# Arduino_S3v3_R2_b.net
KiCad netlist of a schematic drawn in EAGLE
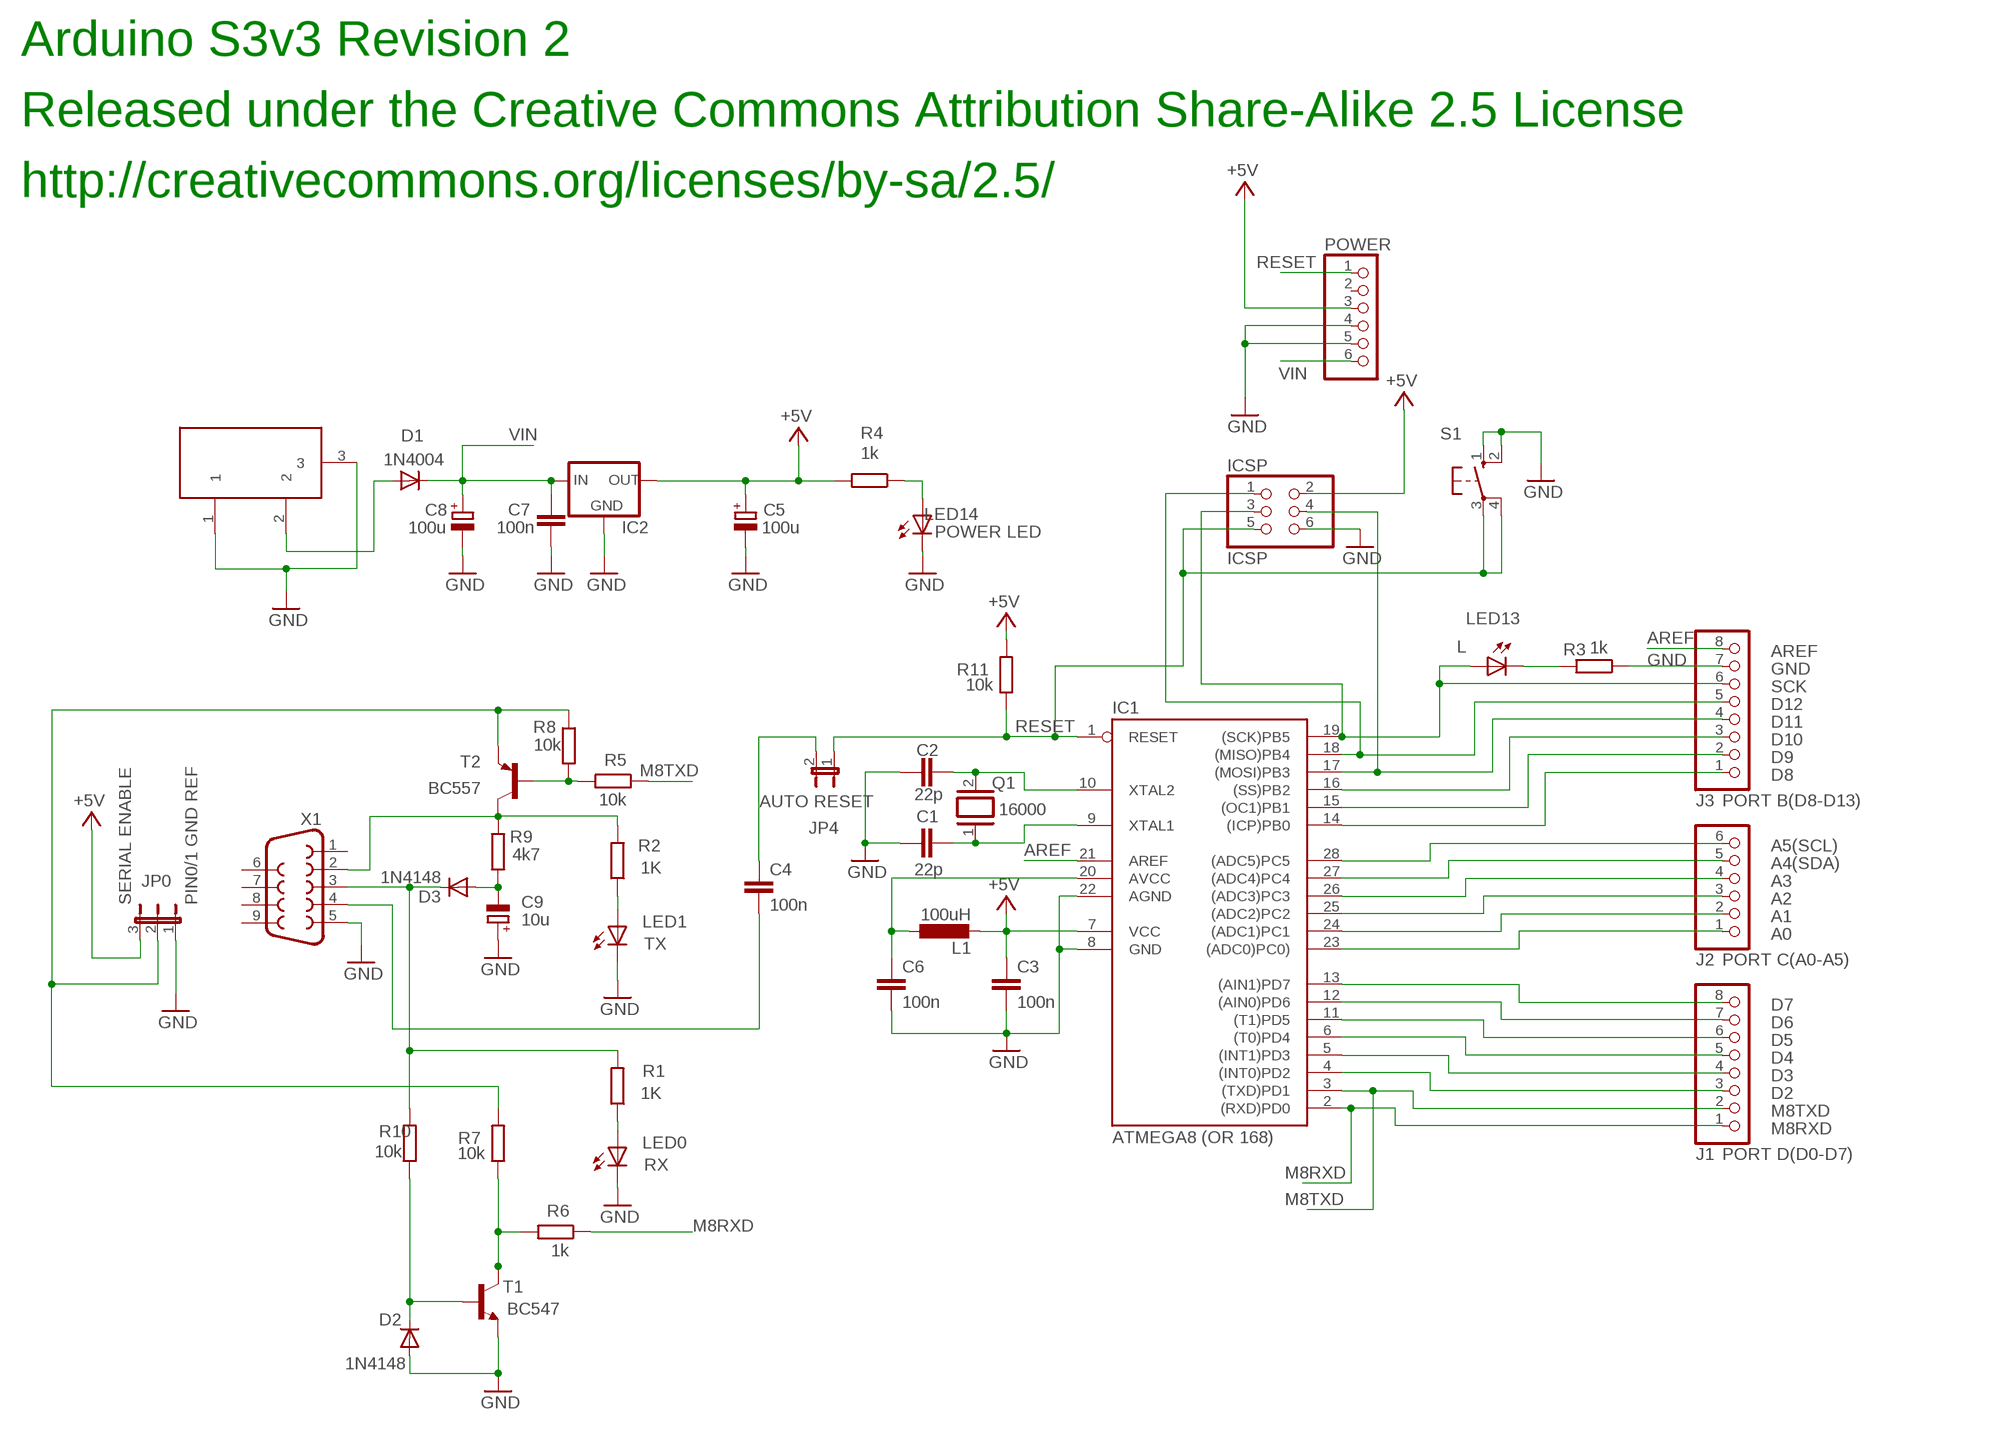
[diagram p0: schematic, sheet 1]

(export (version "E")
  (design (tool "Eeschema 10.0.6"))
  (components
    (comp (ref "C1")
      (value "22p")
      (footprint "eagle-import:C025-024X044")
      (libsource (lib "eagle-import") (part "C-EU025-024X044"))
    )
    (comp (ref "C2")
      (value "22p")
      (footprint "eagle-import:C025-024X044")
      (libsource (lib "eagle-import") (part "C-EU025-024X044"))
    )
    (comp (ref "C3")
      (value "100n")
      (footprint "eagle-import:C050-025X075")
      (libsource (lib "eagle-import") (part "C-EU050-025X075"))
    )
    (comp (ref "C4")
      (value "100n")
      (footprint "eagle-import:C050-025X075")
      (libsource (lib "eagle-import") (part "C-EU050-025X075"))
    )
    (comp (ref "C5")
      (value "100u")
      (footprint "eagle-import:E3,5-8")
      (libsource (lib "eagle-import") (part "CPOL-EUE3.5-8"))
    )
    (comp (ref "C6")
      (value "100n")
      (footprint "eagle-import:C050-025X075")
      (libsource (lib "eagle-import") (part "C-EU050-025X075"))
    )
    (comp (ref "C7")
      (value "100n")
      (footprint "eagle-import:C050-025X075")
      (libsource (lib "eagle-import") (part "C-EU050-025X075"))
    )
    (comp (ref "C8")
      (value "100u")
      (footprint "eagle-import:E3,5-8")
      (libsource (lib "eagle-import") (part "CPOL-EUE3.5-8"))
    )
    (comp (ref "C9")
      (value "10u")
      (footprint "eagle-import:E5-6")
      (libsource (lib "eagle-import") (part "CPOL-EUE5-6"))
    )
    (comp (ref "D1")
      (value "1N4004")
      (footprint "eagle-import:DO41-10")
      (libsource (lib "eagle-import") (part "1N4004"))
    )
    (comp (ref "D2")
      (value "1N4148")
      (footprint "eagle-import:DO35-10")
      (libsource (lib "eagle-import") (part "1N4148"))
    )
    (comp (ref "D3")
      (value "1N4148")
      (footprint "eagle-import:DO35-10")
      (libsource (lib "eagle-import") (part "1N4148"))
    )
    (comp (ref "DC1")
      (value "DC21MMX")
      (footprint "eagle-import:DC-21MM")
      (libsource (lib "eagle-import") (part "DC21MMX"))
    )
    (comp (ref "IC1")
      (value "ATMEGA8 (OR 168)")
      (footprint "eagle-import:DIL28-3")
      (libsource (lib "eagle-import") (part "AT90S4433P"))
    )
    (comp (ref "IC2")
      (value "78XXL")
      (footprint "eagle-import:78XXL")
      (libsource (lib "eagle-import") (part "78XXL"))
    )
    (comp (ref "ICSP")
      (value "ICSP")
      (footprint "eagle-import:2X03")
      (libsource (lib "eagle-import") (part "PINHD-2X3"))
    )
    (comp (ref "J1")
      (value "PORT D(D0-D7)")
      (footprint "eagle-import:1X08")
      (libsource (lib "eagle-import") (part "PINHD-1X8"))
    )
    (comp (ref "J2")
      (value "PORT C(A0-A5)")
      (footprint "eagle-import:1X06")
      (libsource (lib "eagle-import") (part "PINHD-1X6"))
    )
    (comp (ref "J3")
      (value "PORT B(D8-D13)")
      (footprint "eagle-import:1X08")
      (libsource (lib "eagle-import") (part "PINHD-1X8"))
    )
    (comp (ref "JP0")
      (value "JP2W")
      (footprint "eagle-import:JP2W")
      (libsource (lib "eagle-import") (part "JP2W"))
    )
    (comp (ref "JP4")
      (value "AUTO RESET")
      (footprint "eagle-import:JP1W")
      (libsource (lib "eagle-import") (part "JP1W"))
    )
    (comp (ref "L1")
      (value "100uH")
      (footprint "eagle-import:0204_5")
      (libsource (lib "eagle-import") (part "L-EU0204/5"))
    )
    (comp (ref "LED0")
      (value "RX")
      (footprint "eagle-import:LED3MM")
      (libsource (lib "eagle-import") (part "LED3MM"))
    )
    (comp (ref "LED1")
      (value "TX")
      (footprint "eagle-import:LED3MM")
      (libsource (lib "eagle-import") (part "LED3MM"))
    )
    (comp (ref "LED13")
      (value "L")
      (footprint "eagle-import:LED3MM")
      (libsource (lib "eagle-import") (part "LED3MM"))
    )
    (comp (ref "LED14")
      (value "POWER LED")
      (footprint "eagle-import:LED3MM")
      (libsource (lib "eagle-import") (part "LED3MM"))
    )
    (comp (ref "POWER")
      (value "PINHD-1X6")
      (footprint "eagle-import:1X06")
      (libsource (lib "eagle-import") (part "PINHD-1X6"))
    )
    (comp (ref "Q1")
      (value "16000")
      (footprint "eagle-import:QS")
      (libsource (lib "eagle-import") (part "XTAL/S"))
    )
    (comp (ref "R1")
      (value "1K")
      (footprint "eagle-import:0207_10")
      (libsource (lib "eagle-import") (part "R-EU_0207/10"))
    )
    (comp (ref "R2")
      (value "1K")
      (footprint "eagle-import:0207_10")
      (libsource (lib "eagle-import") (part "R-EU_0207/10"))
    )
    (comp (ref "R3")
      (value "1k")
      (footprint "eagle-import:0207_10")
      (libsource (lib "eagle-import") (part "R-EU_0207/10"))
    )
    (comp (ref "R4")
      (value "1k")
      (footprint "eagle-import:0207_10")
      (libsource (lib "eagle-import") (part "R-EU_0207/10"))
    )
    (comp (ref "R5")
      (value "10k")
      (footprint "eagle-import:0207_10")
      (libsource (lib "eagle-import") (part "R-EU_0207/10"))
    )
    (comp (ref "R6")
      (value "1k")
      (footprint "eagle-import:0207_10")
      (libsource (lib "eagle-import") (part "R-EU_0207/10"))
    )
    (comp (ref "R7")
      (value "10k")
      (footprint "eagle-import:0207_10")
      (libsource (lib "eagle-import") (part "R-EU_0207/10"))
    )
    (comp (ref "R8")
      (value "10k")
      (footprint "eagle-import:0207_10")
      (libsource (lib "eagle-import") (part "R-EU_0207/10"))
    )
    (comp (ref "R9")
      (value "4k7")
      (footprint "eagle-import:0207_10")
      (libsource (lib "eagle-import") (part "R-EU_0207/10"))
    )
    (comp (ref "R10")
      (value "10k")
      (footprint "eagle-import:0207_10")
      (libsource (lib "eagle-import") (part "R-EU_0207/10"))
    )
    (comp (ref "R11")
      (value "10k")
      (footprint "eagle-import:0207_10")
      (libsource (lib "eagle-import") (part "R-EU_0207/10"))
    )
    (comp (ref "S1")
      (value "10-XX")
      (footprint "eagle-import:B3F-10XX")
      (libsource (lib "eagle-import") (part "10-XX"))
    )
    (comp (ref "T1")
      (value "BC547")
      (footprint "eagle-import:TO92")
      (libsource (lib "eagle-import") (part "BC547"))
    )
    (comp (ref "T2")
      (value "BC557")
      (footprint "eagle-import:TO92-EBC")
      (libsource (lib "eagle-import") (part "-PNP-TO92-EBCBC557B"))
    )
    (comp (ref "X1")
      (value "F09H")
      (footprint "eagle-import:F09H")
      (libsource (lib "eagle-import") (part "F09H"))
    )
  )
  (nets
    (net (code "1") (name "+5V") (class "Default")
      (node (ref "C3") (pin "1") (pinfunction "1_1") (pintype "passive"))
      (node (ref "C5") (pin "+") (pinfunction "+_+") (pintype "passive"))
      (node (ref "IC1") (pin "7") (pinfunction "VCC_7") (pintype "power_in"))
      (node (ref "IC2") (pin "OUT") (pinfunction "OUT_OUT") (pintype "passive"))
      (node (ref "ICSP") (pin "2") (pinfunction "2_2") (pintype "passive"))
      (node (ref "JP0") (pin "3") (pinfunction "3_3") (pintype "passive"))
      (node (ref "L1") (pin "2") (pinfunction "2_2") (pintype "passive"))
      (node (ref "POWER") (pin "3") (pinfunction "3_3") (pintype "passive"))
      (node (ref "R11") (pin "2") (pinfunction "2_2") (pintype "passive"))
      (node (ref "R4") (pin "2") (pinfunction "2_2") (pintype "passive"))
    )
    (net (code "2") (name "/A0") (class "Default")
      (node (ref "IC1") (pin "23") (pinfunction "(ADC0)PC0)_23") (pintype "bidirectional"))
      (node (ref "J2") (pin "1") (pinfunction "1_1") (pintype "passive"))
    )
    (net (code "3") (name "/A1") (class "Default")
      (node (ref "IC1") (pin "24") (pinfunction "(ADC1)PC1_24") (pintype "bidirectional"))
      (node (ref "J2") (pin "2") (pinfunction "2_2") (pintype "passive"))
    )
    (net (code "4") (name "/A2") (class "Default")
      (node (ref "IC1") (pin "25") (pinfunction "(ADC2)PC2_25") (pintype "bidirectional"))
      (node (ref "J2") (pin "3") (pinfunction "3_3") (pintype "passive"))
    )
    (net (code "5") (name "/A3") (class "Default")
      (node (ref "IC1") (pin "26") (pinfunction "(ADC3)PC3_26") (pintype "bidirectional"))
      (node (ref "J2") (pin "4") (pinfunction "4_4") (pintype "passive"))
    )
    (net (code "6") (name "/A4(SDA)") (class "Default")
      (node (ref "IC1") (pin "27") (pinfunction "(ADC4)PC4_27") (pintype "bidirectional"))
      (node (ref "J2") (pin "5") (pinfunction "5_5") (pintype "passive"))
    )
    (net (code "7") (name "/A5(SCL)") (class "Default")
      (node (ref "IC1") (pin "28") (pinfunction "(ADC5)PC5_28") (pintype "bidirectional"))
      (node (ref "J2") (pin "6") (pinfunction "6_6") (pintype "passive"))
    )
    (net (code "8") (name "/AREF") (class "Default")
      (node (ref "IC1") (pin "21") (pinfunction "AREF_21") (pintype "power_in"))
      (node (ref "J3") (pin "8") (pinfunction "8_8") (pintype "passive"))
    )
    (net (code "9") (name "/D2") (class "Default")
      (node (ref "IC1") (pin "4") (pinfunction "(INT0)PD2_4") (pintype "bidirectional"))
      (node (ref "J1") (pin "3") (pinfunction "3_3") (pintype "passive"))
    )
    (net (code "10") (name "/D3") (class "Default")
      (node (ref "IC1") (pin "5") (pinfunction "(INT1)PD3_5") (pintype "bidirectional"))
      (node (ref "J1") (pin "4") (pinfunction "4_4") (pintype "passive"))
    )
    (net (code "11") (name "/D4") (class "Default")
      (node (ref "IC1") (pin "6") (pinfunction "(T0)PD4_6") (pintype "bidirectional"))
      (node (ref "J1") (pin "5") (pinfunction "5_5") (pintype "passive"))
    )
    (net (code "12") (name "/D5") (class "Default")
      (node (ref "IC1") (pin "11") (pinfunction "(T1)PD5_11") (pintype "bidirectional"))
      (node (ref "J1") (pin "6") (pinfunction "6_6") (pintype "passive"))
    )
    (net (code "13") (name "/D6") (class "Default")
      (node (ref "IC1") (pin "12") (pinfunction "(AIN0)PD6_12") (pintype "bidirectional"))
      (node (ref "J1") (pin "7") (pinfunction "7_7") (pintype "passive"))
    )
    (net (code "14") (name "/D7") (class "Default")
      (node (ref "IC1") (pin "13") (pinfunction "(AIN1)PD7_13") (pintype "bidirectional"))
      (node (ref "J1") (pin "8") (pinfunction "8_8") (pintype "passive"))
    )
    (net (code "15") (name "/D8") (class "Default")
      (node (ref "IC1") (pin "14") (pinfunction "(ICP)PB0_14") (pintype "bidirectional"))
      (node (ref "J3") (pin "1") (pinfunction "1_1") (pintype "passive"))
    )
    (net (code "16") (name "/D9") (class "Default")
      (node (ref "IC1") (pin "15") (pinfunction "(OC1)PB1_15") (pintype "bidirectional"))
      (node (ref "J3") (pin "2") (pinfunction "2_2") (pintype "passive"))
    )
    (net (code "17") (name "/D10") (class "Default")
      (node (ref "IC1") (pin "16") (pinfunction "(SS)PB2_16") (pintype "bidirectional"))
      (node (ref "J3") (pin "3") (pinfunction "3_3") (pintype "passive"))
    )
    (net (code "18") (name "/D11") (class "Default")
      (node (ref "IC1") (pin "17") (pinfunction "(MOSI)PB3_17") (pintype "bidirectional"))
      (node (ref "ICSP") (pin "4") (pinfunction "4_4") (pintype "passive"))
      (node (ref "J3") (pin "4") (pinfunction "4_4") (pintype "passive"))
    )
    (net (code "19") (name "/D12") (class "Default")
      (node (ref "IC1") (pin "18") (pinfunction "(MISO)PB4_18") (pintype "bidirectional"))
      (node (ref "ICSP") (pin "1") (pinfunction "1_1") (pintype "passive"))
      (node (ref "J3") (pin "5") (pinfunction "5_5") (pintype "passive"))
    )
    (net (code "20") (name "/M8RXD") (class "Default")
      (node (ref "IC1") (pin "2") (pinfunction "(RXD)PD0_2") (pintype "bidirectional"))
      (node (ref "J1") (pin "1") (pinfunction "1_1") (pintype "passive"))
      (node (ref "R6") (pin "1") (pinfunction "1_1") (pintype "passive"))
    )
    (net (code "21") (name "/M8TXD") (class "Default")
      (node (ref "IC1") (pin "3") (pinfunction "(TXD)PD1_3") (pintype "bidirectional"))
      (node (ref "J1") (pin "2") (pinfunction "2_2") (pintype "passive"))
      (node (ref "R5") (pin "1") (pinfunction "1_1") (pintype "passive"))
    )
    (net (code "22") (name "/RESET") (class "Default")
      (node (ref "IC1") (pin "1") (pinfunction "RESET_1") (pintype "input"))
      (node (ref "ICSP") (pin "5") (pinfunction "5_5") (pintype "passive"))
      (node (ref "JP4") (pin "1") (pinfunction "1_1") (pintype "passive"))
      (node (ref "POWER") (pin "1") (pinfunction "1_1") (pintype "passive"))
      (node (ref "R11") (pin "1") (pinfunction "1_1") (pintype "passive"))
      (node (ref "S1") (pin "3") (pinfunction "P_3") (pintype "passive"))
      (node (ref "S1") (pin "4") (pinfunction "P1_4") (pintype "passive"))
    )
    (net (code "23") (name "/SCK") (class "Default")
      (node (ref "IC1") (pin "19") (pinfunction "(SCK)PB5_19") (pintype "bidirectional"))
      (node (ref "ICSP") (pin "3") (pinfunction "3_3") (pintype "passive"))
      (node (ref "J3") (pin "6") (pinfunction "6_6") (pintype "passive"))
      (node (ref "LED13") (pin "A") (pinfunction "A_A") (pintype "passive"))
    )
    (net (code "24") (name "/VIN") (class "Default")
      (node (ref "C7") (pin "2") (pinfunction "2_2") (pintype "passive"))
      (node (ref "C8") (pin "+") (pinfunction "+_+") (pintype "passive"))
      (node (ref "D1") (pin "C") (pinfunction "C_C") (pintype "passive"))
      (node (ref "IC2") (pin "IN") (pinfunction "IN_IN") (pintype "input"))
      (node (ref "POWER") (pin "6") (pinfunction "6_6") (pintype "passive"))
    )
    (net (code "25") (name "GND") (class "Default")
      (node (ref "C1") (pin "1") (pinfunction "1_1") (pintype "passive"))
      (node (ref "C2") (pin "1") (pinfunction "1_1") (pintype "passive"))
      (node (ref "C3") (pin "2") (pinfunction "2_2") (pintype "passive"))
      (node (ref "C5") (pin "-") (pinfunction "-_-") (pintype "passive"))
      (node (ref "C6") (pin "2") (pinfunction "2_2") (pintype "passive"))
      (node (ref "C7") (pin "1") (pinfunction "1_1") (pintype "passive"))
      (node (ref "C8") (pin "-") (pinfunction "-_-") (pintype "passive"))
      (node (ref "C9") (pin "+") (pinfunction "+_+") (pintype "passive"))
      (node (ref "D2") (pin "A") (pinfunction "A_A") (pintype "passive"))
      (node (ref "DC1") (pin "1") (pinfunction "1_1") (pintype "power_in"))
      (node (ref "DC1") (pin "3") (pinfunction "3_3") (pintype "power_in"))
      (node (ref "IC1") (pin "22") (pinfunction "AGND_22") (pintype "power_in"))
      (node (ref "IC1") (pin "8") (pinfunction "GND_8") (pintype "power_in"))
      (node (ref "IC2") (pin "GND") (pinfunction "GND_GND") (pintype "input"))
      (node (ref "ICSP") (pin "6") (pinfunction "6_6") (pintype "passive"))
      (node (ref "J3") (pin "7") (pinfunction "7_7") (pintype "passive"))
      (node (ref "JP0") (pin "1") (pinfunction "1_1") (pintype "passive"))
      (node (ref "LED0") (pin "K") (pinfunction "C_K") (pintype "passive"))
      (node (ref "LED1") (pin "K") (pinfunction "C_K") (pintype "passive"))
      (node (ref "LED14") (pin "K") (pinfunction "C_K") (pintype "passive"))
      (node (ref "POWER") (pin "4") (pinfunction "4_4") (pintype "passive"))
      (node (ref "POWER") (pin "5") (pinfunction "5_5") (pintype "passive"))
      (node (ref "R3") (pin "1") (pinfunction "1_1") (pintype "passive"))
      (node (ref "S1") (pin "1") (pinfunction "S_1") (pintype "passive"))
      (node (ref "S1") (pin "2") (pinfunction "S1_2") (pintype "passive"))
      (node (ref "T1") (pin "1") (pinfunction "E_1") (pintype "passive"))
      (node (ref "X1") (pin "5") (pinfunction "5_5") (pintype "passive"))
    )
    (net (code "26") (name "Net-(C4-Pad1)") (class "Default")
      (node (ref "C4") (pin "1") (pinfunction "1_1") (pintype "passive"))
      (node (ref "JP4") (pin "2") (pinfunction "2_2") (pintype "passive"))
    )
    (net (code "27") (name "Net-(C4-Pad2)") (class "Default")
      (node (ref "C4") (pin "2") (pinfunction "2_2") (pintype "passive"))
      (node (ref "X1") (pin "4") (pinfunction "4_4") (pintype "passive"))
    )
    (net (code "28") (name "Net-(C9-Pad-)") (class "Default")
      (node (ref "C9") (pin "-") (pinfunction "-_-") (pintype "passive"))
      (node (ref "D3") (pin "A") (pinfunction "A_A") (pintype "passive"))
      (node (ref "R9") (pin "1") (pinfunction "1_1") (pintype "passive"))
    )
    (net (code "29") (name "Net-(D1-PadA)") (class "Default")
      (node (ref "D1") (pin "A") (pinfunction "A_A") (pintype "passive"))
      (node (ref "DC1") (pin "2") (pinfunction "2_2") (pintype "power_in"))
    )
    (net (code "30") (name "Net-(D3-PadC)") (class "Default")
      (node (ref "D3") (pin "C") (pinfunction "C_C") (pintype "passive"))
      (node (ref "R1") (pin "2") (pinfunction "2_2") (pintype "passive"))
      (node (ref "R10") (pin "2") (pinfunction "2_2") (pintype "passive"))
      (node (ref "X1") (pin "3") (pinfunction "3_3") (pintype "passive"))
    )
    (net (code "31") (name "Net-(IC1-AVCC)") (class "Default")
      (node (ref "C6") (pin "1") (pinfunction "1_1") (pintype "passive"))
      (node (ref "IC1") (pin "20") (pinfunction "AVCC_20") (pintype "power_in"))
      (node (ref "L1") (pin "1") (pinfunction "1_1") (pintype "passive"))
    )
    (net (code "32") (name "Net-(IC1-XTAL1)") (class "Default")
      (node (ref "C1") (pin "2") (pinfunction "2_2") (pintype "passive"))
      (node (ref "IC1") (pin "9") (pinfunction "XTAL1_9") (pintype "bidirectional"))
      (node (ref "Q1") (pin "1") (pinfunction "1_1") (pintype "passive"))
    )
    (net (code "33") (name "Net-(IC1-XTAL2)") (class "Default")
      (node (ref "C2") (pin "2") (pinfunction "2_2") (pintype "passive"))
      (node (ref "IC1") (pin "10") (pinfunction "XTAL2_10") (pintype "bidirectional"))
      (node (ref "Q1") (pin "2") (pinfunction "2_2") (pintype "passive"))
    )
    (net (code "34") (name "Net-(JP0-Pad2)") (class "Default")
      (node (ref "JP0") (pin "2") (pinfunction "2_2") (pintype "passive"))
      (node (ref "R7") (pin "2") (pinfunction "2_2") (pintype "passive"))
      (node (ref "R8") (pin "1") (pinfunction "1_1") (pintype "passive"))
      (node (ref "T2") (pin "E") (pinfunction "E_E") (pintype "passive"))
    )
    (net (code "35") (name "Net-(LED0-PadA)") (class "Default")
      (node (ref "LED0") (pin "A") (pinfunction "A_A") (pintype "passive"))
      (node (ref "R1") (pin "1") (pinfunction "1_1") (pintype "passive"))
    )
    (net (code "36") (name "Net-(LED1-PadA)") (class "Default")
      (node (ref "LED1") (pin "A") (pinfunction "A_A") (pintype "passive"))
      (node (ref "R2") (pin "1") (pinfunction "1_1") (pintype "passive"))
    )
    (net (code "37") (name "Net-(LED13-C)") (class "Default")
      (node (ref "LED13") (pin "K") (pinfunction "C_K") (pintype "passive"))
      (node (ref "R3") (pin "2") (pinfunction "2_2") (pintype "passive"))
    )
    (net (code "38") (name "Net-(LED14-PadA)") (class "Default")
      (node (ref "LED14") (pin "A") (pinfunction "A_A") (pintype "passive"))
      (node (ref "R4") (pin "1") (pinfunction "1_1") (pintype "passive"))
    )
    (net (code "39") (name "Net-(R2-Pad2)") (class "Default")
      (node (ref "R2") (pin "2") (pinfunction "2_2") (pintype "passive"))
      (node (ref "R9") (pin "2") (pinfunction "2_2") (pintype "passive"))
      (node (ref "T2") (pin "C") (pinfunction "C_C") (pintype "passive"))
      (node (ref "X1") (pin "2") (pinfunction "2_2") (pintype "passive"))
    )
    (net (code "40") (name "Net-(R5-Pad2)") (class "Default")
      (node (ref "R5") (pin "2") (pinfunction "2_2") (pintype "passive"))
      (node (ref "R8") (pin "2") (pinfunction "2_2") (pintype "passive"))
      (node (ref "T2") (pin "B") (pinfunction "B_B") (pintype "passive"))
    )
    (net (code "41") (name "Net-(T1-B)") (class "Default")
      (node (ref "D2") (pin "C") (pinfunction "C_C") (pintype "passive"))
      (node (ref "R10") (pin "1") (pinfunction "1_1") (pintype "passive"))
      (node (ref "T1") (pin "2") (pinfunction "B_2") (pintype "passive"))
    )
    (net (code "42") (name "Net-(T1-C)") (class "Default")
      (node (ref "R6") (pin "2") (pinfunction "2_2") (pintype "passive"))
      (node (ref "R7") (pin "1") (pinfunction "1_1") (pintype "passive"))
      (node (ref "T1") (pin "3") (pinfunction "C_3") (pintype "passive"))
    )
    (net (code "43") (name "unconnected-(POWER-Pad2)") (class "Default")
      (node (ref "POWER") (pin "2") (pinfunction "2_2") (pintype "passive"))
    )
    (net (code "44") (name "unconnected-(X1-Pad1)") (class "Default")
      (node (ref "X1") (pin "1") (pinfunction "1_1") (pintype "passive"))
    )
    (net (code "45") (name "unconnected-(X1-Pad6)") (class "Default")
      (node (ref "X1") (pin "6") (pinfunction "6_6") (pintype "passive"))
    )
    (net (code "46") (name "unconnected-(X1-Pad7)") (class "Default")
      (node (ref "X1") (pin "7") (pinfunction "7_7") (pintype "passive"))
    )
    (net (code "47") (name "unconnected-(X1-Pad8)") (class "Default")
      (node (ref "X1") (pin "8") (pinfunction "8_8") (pintype "passive"))
    )
    (net (code "48") (name "unconnected-(X1-Pad9)") (class "Default")
      (node (ref "X1") (pin "9") (pinfunction "9_9") (pintype "passive"))
    )
  )
)
